# SCH_Sesame-Distro-Board-V2_2026-03-06.net
KiCad netlist of a schematic drawn in EasyEDA
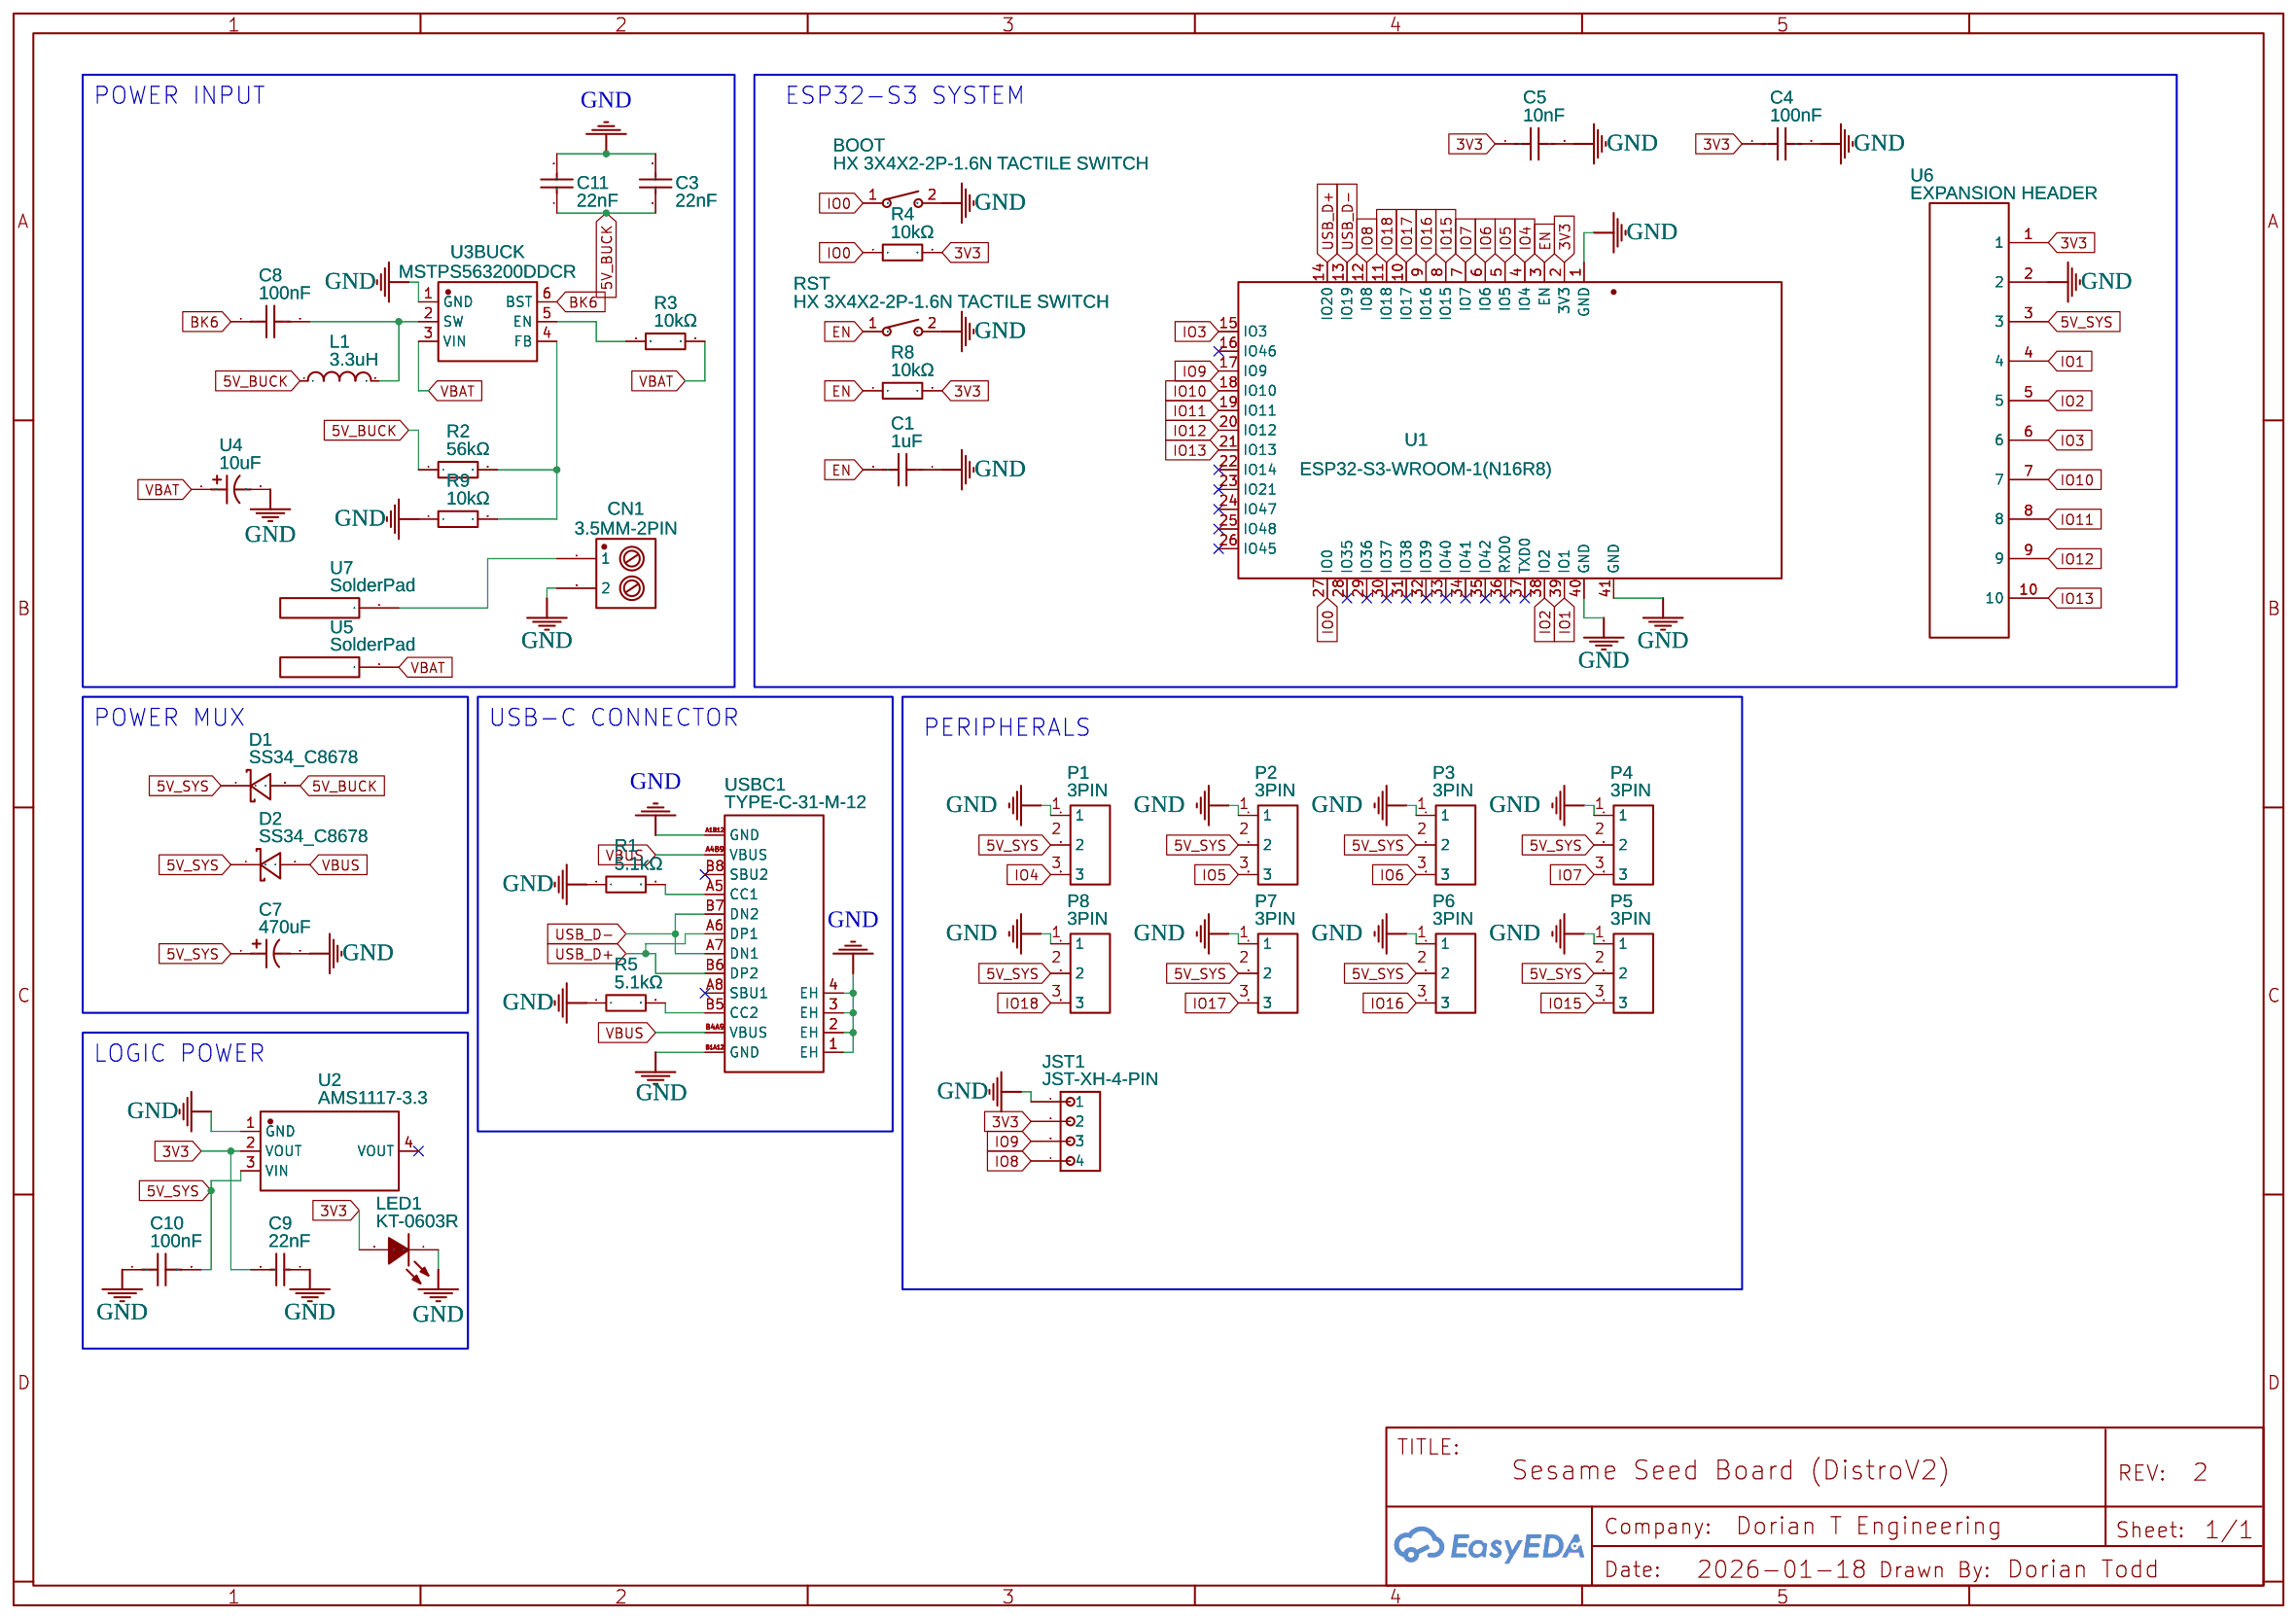
[diagram p0: schematic sheet]

(export (version "E")
  (design (tool "Eeschema 10.0.6"))
  (components
    (comp (ref "BOOT")
      (value "HX 3X4X2-2P-1.6N TACTILE SWITCH")
      (fields
        (field (name "Manufacturer Part") "HX 3x4x2-2P-1.6N TACTILE SWITCH")
        (field (name "Manufacturer") "hanxia(韩下)")
      )
      (libsource (lib "") (part "HX 3X4X2-2P-1.6N TACTILE SWITCH"))
    )
    (comp (ref "C1")
      (value "1uF")
      (fields
        (field (name "Manufacturer Part") "AC0805KKX7R9BB105")
        (field (name "Manufacturer") "YAGEO(国巨)")
      )
      (libsource (lib "") (part "AC0805KKX7R9BB105"))
    )
    (comp (ref "C3")
      (value "22nF")
      (fields
        (field (name "Manufacturer Part") "CL10B223KB8NNNC")
        (field (name "Manufacturer") "SAMSUNG(三星)")
      )
      (libsource (lib "") (part "CL10B223KB8NNNC"))
    )
    (comp (ref "C4")
      (value "100nF")
      (fields
        (field (name "Manufacturer Part") "CC0603KRX7R9BB104")
        (field (name "Manufacturer") "YAGEO(国巨)")
      )
      (libsource (lib "") (part "CC0603KRX7R9BB104"))
    )
    (comp (ref "C5")
      (value "10nF")
      (fields (field (name "Manufacturer Part") "C0603B103M500NT") (field (name "Manufacturer") "TORCH(火炬)"))
      (libsource (lib "") (part "C0603B103M500NT"))
    )
    (comp (ref "C7")
      (value "470uF")
      (fields
        (field (name "Manufacturer Part") "XT470UF25V90RV0111")
        (field (name "Manufacturer") "KNSCHA(科尼盛)")
      )
      (libsource (lib "") (part "XT470UF25V90RV0111"))
    )
    (comp (ref "C8")
      (value "100nF")
      (fields
        (field (name "Manufacturer Part") "CC0603KRX7R9BB104")
        (field (name "Manufacturer") "YAGEO(国巨)")
      )
      (libsource (lib "") (part "CC0603KRX7R9BB104"))
    )
    (comp (ref "C9")
      (value "22nF")
      (fields
        (field (name "Manufacturer Part") "CL10B223KB8NNNC")
        (field (name "Manufacturer") "SAMSUNG(三星)")
      )
      (libsource (lib "") (part "CL10B223KB8NNNC_1"))
    )
    (comp (ref "C10")
      (value "100nF")
      (fields
        (field (name "Manufacturer Part") "CC0603KRX7R9BB104")
        (field (name "Manufacturer") "YAGEO(国巨)")
      )
      (libsource (lib "") (part "CC0603KRX7R9BB104"))
    )
    (comp (ref "C11")
      (value "22nF")
      (fields
        (field (name "Manufacturer Part") "CL10B223KB8NNNC")
        (field (name "Manufacturer") "SAMSUNG(三星)")
      )
      (libsource (lib "") (part "CL10B223KB8NNNC"))
    )
    (comp (ref "CN1")
      (value "3.5MM-2PIN")
      (fields (field (name "Manufacturer Part") "1984617") (field (name "Manufacturer") "Phoenix Contact"))
      (libsource (lib "") (part "SCREWTERM-RA-3.5MM-2PIN"))
    )
    (comp (ref "D1")
      (value "SS34_C8678")
      (fields (field (name "Manufacturer Part") "SS34") (field (name "Manufacturer") "MDD(辰达半导体)"))
      (libsource (lib "") (part "SS34_C8678"))
    )
    (comp (ref "D2")
      (value "SS34_C8678")
      (fields (field (name "Manufacturer Part") "SS34") (field (name "Manufacturer") "MDD(辰达半导体)"))
      (libsource (lib "") (part "SS34_C8678"))
    )
    (comp (ref "JST1") (value "JST-XH-4-PIN") (libsource (lib "") (part "JST-XH-4-PIN")))
    (comp (ref "L1")
      (value "3.3uH")
      (fields
        (field (name "Manufacturer Part") "MHCI06030-3R3M-S8")
        (field (name "Manufacturer") "Chilisin(奇力新)")
      )
      (libsource (lib "") (part "MHCI06030-3R3M-S8"))
    )
    (comp (ref "LED1")
      (value "KT-0603R")
      (fields (field (name "Manufacturer") "KENTO"))
      (libsource (lib "") (part "KT-0603R"))
    )
    (comp (ref "P1")
      (value "3PIN")
      (fields
        (field (name "Manufacturer Part") "Female headerHDR1X8-2.54")
        (field (name "Manufacturer") "BOOMELE")
      )
      (libsource (lib "") (part "HEADER PAD 3 PIN"))
    )
    (comp (ref "P2")
      (value "3PIN")
      (fields
        (field (name "Manufacturer Part") "Female headerHDR1X8-2.54")
        (field (name "Manufacturer") "BOOMELE")
      )
      (libsource (lib "") (part "HEADER PAD 3 PIN"))
    )
    (comp (ref "P3")
      (value "3PIN")
      (fields
        (field (name "Manufacturer Part") "Female headerHDR1X8-2.54")
        (field (name "Manufacturer") "BOOMELE")
      )
      (libsource (lib "") (part "HEADER PAD 3 PIN"))
    )
    (comp (ref "P4")
      (value "3PIN")
      (fields
        (field (name "Manufacturer Part") "Female headerHDR1X8-2.54")
        (field (name "Manufacturer") "BOOMELE")
      )
      (libsource (lib "") (part "HEADER PAD 3 PIN"))
    )
    (comp (ref "P5")
      (value "3PIN")
      (fields
        (field (name "Manufacturer Part") "Female headerHDR1X8-2.54")
        (field (name "Manufacturer") "BOOMELE")
      )
      (libsource (lib "") (part "HEADER PAD 3 PIN"))
    )
    (comp (ref "P6")
      (value "3PIN")
      (fields
        (field (name "Manufacturer Part") "Female headerHDR1X8-2.54")
        (field (name "Manufacturer") "BOOMELE")
      )
      (libsource (lib "") (part "HEADER PAD 3 PIN"))
    )
    (comp (ref "P7")
      (value "3PIN")
      (fields
        (field (name "Manufacturer Part") "Female headerHDR1X8-2.54")
        (field (name "Manufacturer") "BOOMELE")
      )
      (libsource (lib "") (part "HEADER PAD 3 PIN"))
    )
    (comp (ref "P8")
      (value "3PIN")
      (fields
        (field (name "Manufacturer Part") "Female headerHDR1X8-2.54")
        (field (name "Manufacturer") "BOOMELE")
      )
      (libsource (lib "") (part "HEADER PAD 3 PIN"))
    )
    (comp (ref "R1")
      (value "5.1kΩ")
      (fields
        (field (name "Manufacturer Part") "0603WAF5101T5E")
        (field (name "Manufacturer") "UNI-ROYAL(厚声)")
      )
      (libsource (lib "") (part "0603WAF5101T5E"))
    )
    (comp (ref "R2")
      (value "56kΩ")
      (fields
        (field (name "Manufacturer Part") "0603WAF5602T5E")
        (field (name "Manufacturer") "UNI-ROYAL(厚声)")
      )
      (libsource (lib "") (part "0603WAF5602T5E"))
    )
    (comp (ref "R3")
      (value "10kΩ")
      (fields (field (name "Manufacturer Part") "RCT0310KJLF") (field (name "Manufacturer") "HKR(香港电阻)"))
      (libsource (lib "") (part "RCT0310KJLF"))
    )
    (comp (ref "R4")
      (value "10kΩ")
      (fields (field (name "Manufacturer Part") "RCT0310KJLF") (field (name "Manufacturer") "HKR(香港电阻)"))
      (libsource (lib "") (part "RCT0310KJLF"))
    )
    (comp (ref "R5")
      (value "5.1kΩ")
      (fields
        (field (name "Manufacturer Part") "0603WAF5101T5E")
        (field (name "Manufacturer") "UNI-ROYAL(厚声)")
      )
      (libsource (lib "") (part "0603WAF5101T5E"))
    )
    (comp (ref "R8")
      (value "10kΩ")
      (fields (field (name "Manufacturer Part") "RCT0310KJLF") (field (name "Manufacturer") "HKR(香港电阻)"))
      (libsource (lib "") (part "RCT0310KJLF"))
    )
    (comp (ref "R9")
      (value "10kΩ")
      (fields (field (name "Manufacturer Part") "RCT0310KJLF") (field (name "Manufacturer") "HKR(香港电阻)"))
      (libsource (lib "") (part "RCT0310KJLF"))
    )
    (comp (ref "RST")
      (value "HX 3X4X2-2P-1.6N TACTILE SWITCH")
      (fields
        (field (name "Manufacturer Part") "HX 3x4x2-2P-1.6N TACTILE SWITCH")
        (field (name "Manufacturer") "hanxia(韩下)")
      )
      (libsource (lib "") (part "HX 3X4X2-2P-1.6N TACTILE SWITCH_1"))
    )
    (comp (ref "U1")
      (value "ESP32-S3-WROOM-1(N16R8)")
      (fields
        (field (name "Manufacturer Part") "ESP32-S3-WROOM-1-N16R8")
        (field (name "Manufacturer") "ESPRESSIF(乐鑫)")
      )
      (libsource (lib "") (part "ESP32-S3-WROOM-1(N16R8)"))
    )
    (comp (ref "U2")
      (value "AMS1117-3.3")
      (fields (field (name "Manufacturer") "AMS"))
      (libsource (lib "") (part "AMS1117-3.3"))
    )
    (comp (ref "U3BUCK")
      (value "MSTPS563200DDCR")
      (fields (field (name "Manufacturer") "MSKSEMI(美森科)"))
      (libsource (lib "") (part "MSTPS563200DDCR"))
    )
    (comp (ref "U4")
      (value "10uF")
      (fields (field (name "Manufacturer Part") "RST10UF25V014") (field (name "Manufacturer") "KNSCHA(科尼盛)"))
      (libsource (lib "") (part "RST10UF25V014"))
    )
    (comp (ref "U5") (value "SolderPad") (libsource (lib "") (part "SolderPad")))
    (comp (ref "U6") (value "EXPANSION HEADER") (libsource (lib "") (part "HEADER MALE 2.54-1*10")))
    (comp (ref "U7") (value "SolderPad") (libsource (lib "") (part "SolderPad")))
    (comp (ref "USBC1")
      (value "TYPE-C-31-M-12")
      (fields (field (name "Manufacturer") "韩国韩荣"))
      (libsource (lib "") (part "TYPE-C-31-M-12"))
    )
  )
  (nets
    (net (code "1") (name "3V3") (class "Default")
      (node (ref "C4") (pin "1") (pinfunction "1_1") (pintype "unspecified"))
      (node (ref "C5") (pin "1") (pinfunction "1_1") (pintype "unspecified"))
      (node (ref "C9") (pin "2") (pinfunction "2_2") (pintype "input"))
      (node (ref "JST1") (pin "2") (pinfunction "2_2") (pintype "unspecified"))
      (node (ref "LED1") (pin "2") (pinfunction "A_2") (pintype "unspecified"))
      (node (ref "R4") (pin "2") (pinfunction "2_2") (pintype "unspecified"))
      (node (ref "R8") (pin "2") (pinfunction "2_2") (pintype "unspecified"))
      (node (ref "U1") (pin "2") (pinfunction "3V3_2") (pintype "unspecified"))
      (node (ref "U2") (pin "2") (pinfunction "VOUT_2") (pintype "unspecified"))
      (node (ref "U6") (pin "1") (pinfunction "1_1") (pintype "unspecified"))
    )
    (net (code "2") (name "5V_BUCK") (class "Default")
      (node (ref "C11") (pin "1") (pinfunction "1_1") (pintype "input"))
      (node (ref "C3") (pin "1") (pinfunction "1_1") (pintype "input"))
      (node (ref "D1") (pin "2") (pinfunction "A_2") (pintype "unspecified"))
      (node (ref "L1") (pin "1") (pinfunction "1_1") (pintype "unspecified"))
      (node (ref "R2") (pin "1") (pinfunction "1_1") (pintype "input"))
    )
    (net (code "3") (name "5V_SYS") (class "Default")
      (node (ref "C10") (pin "2") (pinfunction "2_2") (pintype "unspecified"))
      (node (ref "C7") (pin "1") (pinfunction "1_1") (pintype "input"))
      (node (ref "D1") (pin "1") (pinfunction "K_1") (pintype "unspecified"))
      (node (ref "D2") (pin "1") (pinfunction "K_1") (pintype "unspecified"))
      (node (ref "P1") (pin "2") (pinfunction "2_2") (pintype "unspecified"))
      (node (ref "P2") (pin "2") (pinfunction "2_2") (pintype "unspecified"))
      (node (ref "P3") (pin "2") (pinfunction "2_2") (pintype "unspecified"))
      (node (ref "P4") (pin "2") (pinfunction "2_2") (pintype "unspecified"))
      (node (ref "P5") (pin "2") (pinfunction "2_2") (pintype "unspecified"))
      (node (ref "P6") (pin "2") (pinfunction "2_2") (pintype "unspecified"))
      (node (ref "P7") (pin "2") (pinfunction "2_2") (pintype "unspecified"))
      (node (ref "P8") (pin "2") (pinfunction "2_2") (pintype "unspecified"))
      (node (ref "U2") (pin "3") (pinfunction "VIN_3") (pintype "unspecified"))
      (node (ref "U6") (pin "3") (pinfunction "3_3") (pintype "unspecified"))
    )
    (net (code "4") (name "BK6") (class "Default")
      (node (ref "C8") (pin "1") (pinfunction "1_1") (pintype "unspecified"))
      (node (ref "U3BUCK") (pin "6") (pinfunction "BST_6") (pintype "unspecified"))
    )
    (net (code "5") (name "EN") (class "Default")
      (node (ref "C1") (pin "2") (pinfunction "2_2") (pintype "unspecified"))
      (node (ref "R8") (pin "1") (pinfunction "1_1") (pintype "unspecified"))
      (node (ref "RST") (pin "1") (pinfunction "1_1") (pintype "unspecified"))
      (node (ref "U1") (pin "3") (pinfunction "EN_3") (pintype "unspecified"))
    )
    (net (code "6") (name "GND") (class "Default")
      (node (ref "BOOT") (pin "2") (pinfunction "2_2") (pintype "unspecified"))
      (node (ref "C1") (pin "1") (pinfunction "1_1") (pintype "unspecified"))
      (node (ref "C10") (pin "1") (pinfunction "1_1") (pintype "unspecified"))
      (node (ref "C11") (pin "2") (pinfunction "2_2") (pintype "input"))
      (node (ref "C3") (pin "2") (pinfunction "2_2") (pintype "input"))
      (node (ref "C4") (pin "2") (pinfunction "2_2") (pintype "unspecified"))
      (node (ref "C5") (pin "2") (pinfunction "2_2") (pintype "unspecified"))
      (node (ref "C7") (pin "2") (pinfunction "2_2") (pintype "input"))
      (node (ref "C9") (pin "1") (pinfunction "1_1") (pintype "input"))
      (node (ref "CN1") (pin "2") (pinfunction "2_2") (pintype "unspecified"))
      (node (ref "JST1") (pin "1") (pinfunction "1_1") (pintype "unspecified"))
      (node (ref "LED1") (pin "1") (pinfunction "K_1") (pintype "unspecified"))
      (node (ref "P1") (pin "1") (pinfunction "1_1") (pintype "unspecified"))
      (node (ref "P2") (pin "1") (pinfunction "1_1") (pintype "unspecified"))
      (node (ref "P3") (pin "1") (pinfunction "1_1") (pintype "unspecified"))
      (node (ref "P4") (pin "1") (pinfunction "1_1") (pintype "unspecified"))
      (node (ref "P5") (pin "1") (pinfunction "1_1") (pintype "unspecified"))
      (node (ref "P6") (pin "1") (pinfunction "1_1") (pintype "unspecified"))
      (node (ref "P7") (pin "1") (pinfunction "1_1") (pintype "unspecified"))
      (node (ref "P8") (pin "1") (pinfunction "1_1") (pintype "unspecified"))
      (node (ref "R1") (pin "1") (pinfunction "1_1") (pintype "input"))
      (node (ref "R5") (pin "1") (pinfunction "1_1") (pintype "input"))
      (node (ref "R9") (pin "1") (pinfunction "1_1") (pintype "unspecified"))
      (node (ref "RST") (pin "2") (pinfunction "2_2") (pintype "unspecified"))
      (node (ref "U1") (pin "1") (pinfunction "GND_1") (pintype "unspecified"))
      (node (ref "U1") (pin "40") (pinfunction "GND_40") (pintype "unspecified"))
      (node (ref "U1") (pin "41") (pinfunction "GND_41") (pintype "unspecified"))
      (node (ref "U2") (pin "1") (pinfunction "GND_1") (pintype "unspecified"))
      (node (ref "U3BUCK") (pin "1") (pinfunction "GND_1") (pintype "unspecified"))
      (node (ref "U4") (pin "2") (pinfunction "2_2") (pintype "input"))
      (node (ref "U6") (pin "2") (pinfunction "2_2") (pintype "unspecified"))
      (node (ref "USBC1") (pin "1") (pinfunction "EH_1") (pintype "unspecified"))
      (node (ref "USBC1") (pin "2") (pinfunction "EH_2") (pintype "unspecified"))
      (node (ref "USBC1") (pin "3") (pinfunction "EH_3") (pintype "unspecified"))
      (node (ref "USBC1") (pin "4") (pinfunction "EH_4") (pintype "unspecified"))
      (node (ref "USBC1") (pin "A1B12") (pinfunction "GND_A1B12") (pintype "unspecified"))
      (node (ref "USBC1") (pin "B1A12") (pinfunction "GND_B1A12") (pintype "unspecified"))
    )
    (net (code "7") (name "IO0") (class "Default")
      (node (ref "BOOT") (pin "1") (pinfunction "1_1") (pintype "unspecified"))
      (node (ref "R4") (pin "1") (pinfunction "1_1") (pintype "unspecified"))
      (node (ref "U1") (pin "27") (pinfunction "IO0_27") (pintype "unspecified"))
    )
    (net (code "8") (name "IO1") (class "Default")
      (node (ref "U1") (pin "39") (pinfunction "IO1_39") (pintype "unspecified"))
      (node (ref "U6") (pin "4") (pinfunction "4_4") (pintype "unspecified"))
    )
    (net (code "9") (name "IO2") (class "Default")
      (node (ref "U1") (pin "38") (pinfunction "IO2_38") (pintype "unspecified"))
      (node (ref "U6") (pin "5") (pinfunction "5_5") (pintype "unspecified"))
    )
    (net (code "10") (name "IO3") (class "Default")
      (node (ref "U1") (pin "15") (pinfunction "IO3_15") (pintype "unspecified"))
      (node (ref "U6") (pin "6") (pinfunction "6_6") (pintype "unspecified"))
    )
    (net (code "11") (name "IO4") (class "Default")
      (node (ref "P1") (pin "3") (pinfunction "3_3") (pintype "unspecified"))
      (node (ref "U1") (pin "4") (pinfunction "IO4_4") (pintype "unspecified"))
    )
    (net (code "12") (name "IO5") (class "Default")
      (node (ref "P2") (pin "3") (pinfunction "3_3") (pintype "unspecified"))
      (node (ref "U1") (pin "5") (pinfunction "IO5_5") (pintype "unspecified"))
    )
    (net (code "13") (name "IO6") (class "Default")
      (node (ref "P3") (pin "3") (pinfunction "3_3") (pintype "unspecified"))
      (node (ref "U1") (pin "6") (pinfunction "IO6_6") (pintype "unspecified"))
    )
    (net (code "14") (name "IO7") (class "Default")
      (node (ref "P4") (pin "3") (pinfunction "3_3") (pintype "unspecified"))
      (node (ref "U1") (pin "7") (pinfunction "IO7_7") (pintype "unspecified"))
    )
    (net (code "15") (name "IO8") (class "Default")
      (node (ref "JST1") (pin "4") (pinfunction "4_4") (pintype "unspecified"))
      (node (ref "U1") (pin "12") (pinfunction "IO8_12") (pintype "unspecified"))
    )
    (net (code "16") (name "IO9") (class "Default")
      (node (ref "JST1") (pin "3") (pinfunction "3_3") (pintype "unspecified"))
      (node (ref "U1") (pin "17") (pinfunction "IO9_17") (pintype "unspecified"))
    )
    (net (code "17") (name "IO10") (class "Default")
      (node (ref "U1") (pin "18") (pinfunction "IO10_18") (pintype "unspecified"))
      (node (ref "U6") (pin "7") (pinfunction "7_7") (pintype "unspecified"))
    )
    (net (code "18") (name "IO11") (class "Default")
      (node (ref "U1") (pin "19") (pinfunction "IO11_19") (pintype "unspecified"))
      (node (ref "U6") (pin "8") (pinfunction "8_8") (pintype "unspecified"))
    )
    (net (code "19") (name "IO12") (class "Default")
      (node (ref "U1") (pin "20") (pinfunction "IO12_20") (pintype "unspecified"))
      (node (ref "U6") (pin "9") (pinfunction "9_9") (pintype "unspecified"))
    )
    (net (code "20") (name "IO13") (class "Default")
      (node (ref "U1") (pin "21") (pinfunction "IO13_21") (pintype "unspecified"))
      (node (ref "U6") (pin "10") (pinfunction "10_10") (pintype "unspecified"))
    )
    (net (code "21") (name "IO15") (class "Default")
      (node (ref "P5") (pin "3") (pinfunction "3_3") (pintype "unspecified"))
      (node (ref "U1") (pin "8") (pinfunction "IO15_8") (pintype "unspecified"))
    )
    (net (code "22") (name "IO16") (class "Default")
      (node (ref "P6") (pin "3") (pinfunction "3_3") (pintype "unspecified"))
      (node (ref "U1") (pin "9") (pinfunction "IO16_9") (pintype "unspecified"))
    )
    (net (code "23") (name "IO17") (class "Default")
      (node (ref "P7") (pin "3") (pinfunction "3_3") (pintype "unspecified"))
      (node (ref "U1") (pin "10") (pinfunction "IO17_10") (pintype "unspecified"))
    )
    (net (code "24") (name "IO18") (class "Default")
      (node (ref "P8") (pin "3") (pinfunction "3_3") (pintype "unspecified"))
      (node (ref "U1") (pin "11") (pinfunction "IO18_11") (pintype "unspecified"))
    )
    (net (code "25") (name "Net-(CN1-Pad1)") (class "Default")
      (node (ref "CN1") (pin "1") (pinfunction "1_1") (pintype "unspecified"))
      (node (ref "U7") (pin "1") (pinfunction "1_1") (pintype "unspecified"))
    )
    (net (code "26") (name "Net-(U3BUCK-EN)") (class "Default")
      (node (ref "R3") (pin "1") (pinfunction "1_1") (pintype "unspecified"))
      (node (ref "U3BUCK") (pin "5") (pinfunction "EN_5") (pintype "unspecified"))
    )
    (net (code "27") (name "Net-(U3BUCK-FB)") (class "Default")
      (node (ref "R2") (pin "2") (pinfunction "2_2") (pintype "input"))
      (node (ref "R9") (pin "2") (pinfunction "2_2") (pintype "unspecified"))
      (node (ref "U3BUCK") (pin "4") (pinfunction "FB_4") (pintype "unspecified"))
    )
    (net (code "28") (name "Net-(U3BUCK-SW)") (class "Default")
      (node (ref "C8") (pin "2") (pinfunction "2_2") (pintype "unspecified"))
      (node (ref "L1") (pin "2") (pinfunction "2_2") (pintype "unspecified"))
      (node (ref "U3BUCK") (pin "2") (pinfunction "SW_2") (pintype "unspecified"))
    )
    (net (code "29") (name "Net-(USBC1-CC1)") (class "Default")
      (node (ref "R1") (pin "2") (pinfunction "2_2") (pintype "input"))
      (node (ref "USBC1") (pin "A5") (pinfunction "CC1_A5") (pintype "unspecified"))
    )
    (net (code "30") (name "Net-(USBC1-CC2)") (class "Default")
      (node (ref "R5") (pin "2") (pinfunction "2_2") (pintype "input"))
      (node (ref "USBC1") (pin "B5") (pinfunction "CC2_B5") (pintype "unspecified"))
    )
    (net (code "31") (name "USB_D+") (class "Default")
      (node (ref "U1") (pin "14") (pinfunction "IO20_14") (pintype "unspecified"))
      (node (ref "USBC1") (pin "A6") (pinfunction "DP1_A6") (pintype "unspecified"))
      (node (ref "USBC1") (pin "B6") (pinfunction "DP2_B6") (pintype "unspecified"))
    )
    (net (code "32") (name "USB_D-") (class "Default")
      (node (ref "U1") (pin "13") (pinfunction "IO19_13") (pintype "unspecified"))
      (node (ref "USBC1") (pin "A7") (pinfunction "DN1_A7") (pintype "unspecified"))
      (node (ref "USBC1") (pin "B7") (pinfunction "DN2_B7") (pintype "unspecified"))
    )
    (net (code "33") (name "VBAT") (class "Default")
      (node (ref "R3") (pin "2") (pinfunction "2_2") (pintype "unspecified"))
      (node (ref "U3BUCK") (pin "3") (pinfunction "VIN_3") (pintype "unspecified"))
      (node (ref "U4") (pin "1") (pinfunction "1_1") (pintype "input"))
      (node (ref "U5") (pin "1") (pinfunction "1_1") (pintype "unspecified"))
    )
    (net (code "34") (name "VBUS") (class "Default")
      (node (ref "D2") (pin "2") (pinfunction "A_2") (pintype "unspecified"))
      (node (ref "USBC1") (pin "A4B9") (pinfunction "VBUS_A4B9") (pintype "unspecified"))
      (node (ref "USBC1") (pin "B4A9") (pinfunction "VBUS_B4A9") (pintype "unspecified"))
    )
    (net (code "35") (name "unconnected-(U1-IO14-Pad22)") (class "Default")
      (node (ref "U1") (pin "22") (pinfunction "IO14_22") (pintype "unspecified+no_connect"))
    )
    (net (code "36") (name "unconnected-(U1-IO21-Pad23)") (class "Default")
      (node (ref "U1") (pin "23") (pinfunction "IO21_23") (pintype "unspecified+no_connect"))
    )
    (net (code "37") (name "unconnected-(U1-IO35-Pad28)") (class "Default")
      (node (ref "U1") (pin "28") (pinfunction "IO35_28") (pintype "unspecified+no_connect"))
    )
    (net (code "38") (name "unconnected-(U1-IO36-Pad29)") (class "Default")
      (node (ref "U1") (pin "29") (pinfunction "IO36_29") (pintype "unspecified+no_connect"))
    )
    (net (code "39") (name "unconnected-(U1-IO37-Pad30)") (class "Default")
      (node (ref "U1") (pin "30") (pinfunction "IO37_30") (pintype "unspecified+no_connect"))
    )
    (net (code "40") (name "unconnected-(U1-IO38-Pad31)") (class "Default")
      (node (ref "U1") (pin "31") (pinfunction "IO38_31") (pintype "unspecified+no_connect"))
    )
    (net (code "41") (name "unconnected-(U1-IO39-Pad32)") (class "Default")
      (node (ref "U1") (pin "32") (pinfunction "IO39_32") (pintype "unspecified+no_connect"))
    )
    (net (code "42") (name "unconnected-(U1-IO40-Pad33)") (class "Default")
      (node (ref "U1") (pin "33") (pinfunction "IO40_33") (pintype "unspecified+no_connect"))
    )
    (net (code "43") (name "unconnected-(U1-IO41-Pad34)") (class "Default")
      (node (ref "U1") (pin "34") (pinfunction "IO41_34") (pintype "unspecified+no_connect"))
    )
    (net (code "44") (name "unconnected-(U1-IO42-Pad35)") (class "Default")
      (node (ref "U1") (pin "35") (pinfunction "IO42_35") (pintype "unspecified+no_connect"))
    )
    (net (code "45") (name "unconnected-(U1-IO45-Pad26)") (class "Default")
      (node (ref "U1") (pin "26") (pinfunction "IO45_26") (pintype "unspecified+no_connect"))
    )
    (net (code "46") (name "unconnected-(U1-IO46-Pad16)") (class "Default")
      (node (ref "U1") (pin "16") (pinfunction "IO46_16") (pintype "unspecified+no_connect"))
    )
    (net (code "47") (name "unconnected-(U1-IO47-Pad24)") (class "Default")
      (node (ref "U1") (pin "24") (pinfunction "IO47_24") (pintype "unspecified+no_connect"))
    )
    (net (code "48") (name "unconnected-(U1-IO48-Pad25)") (class "Default")
      (node (ref "U1") (pin "25") (pinfunction "IO48_25") (pintype "unspecified+no_connect"))
    )
    (net (code "49") (name "unconnected-(U1-RXD0-Pad36)") (class "Default")
      (node (ref "U1") (pin "36") (pinfunction "RXD0_36") (pintype "unspecified+no_connect"))
    )
    (net (code "50") (name "unconnected-(U1-TXD0-Pad37)") (class "Default")
      (node (ref "U1") (pin "37") (pinfunction "TXD0_37") (pintype "unspecified+no_connect"))
    )
    (net (code "51") (name "unconnected-(U2-VOUT-Pad4)") (class "Default")
      (node (ref "U2") (pin "4") (pinfunction "VOUT_4") (pintype "unspecified+no_connect"))
    )
    (net (code "52") (name "unconnected-(USBC1-SBU1-PadA8)") (class "Default")
      (node (ref "USBC1") (pin "A8") (pinfunction "SBU1_A8") (pintype "unspecified+no_connect"))
    )
    (net (code "53") (name "unconnected-(USBC1-SBU2-PadB8)") (class "Default")
      (node (ref "USBC1") (pin "B8") (pinfunction "SBU2_B8") (pintype "unspecified+no_connect"))
    )
  )
)
